# TPS53319_1_2V_Buck_Converter.net
KiCad netlist of a schematic drawn in Altium Designer
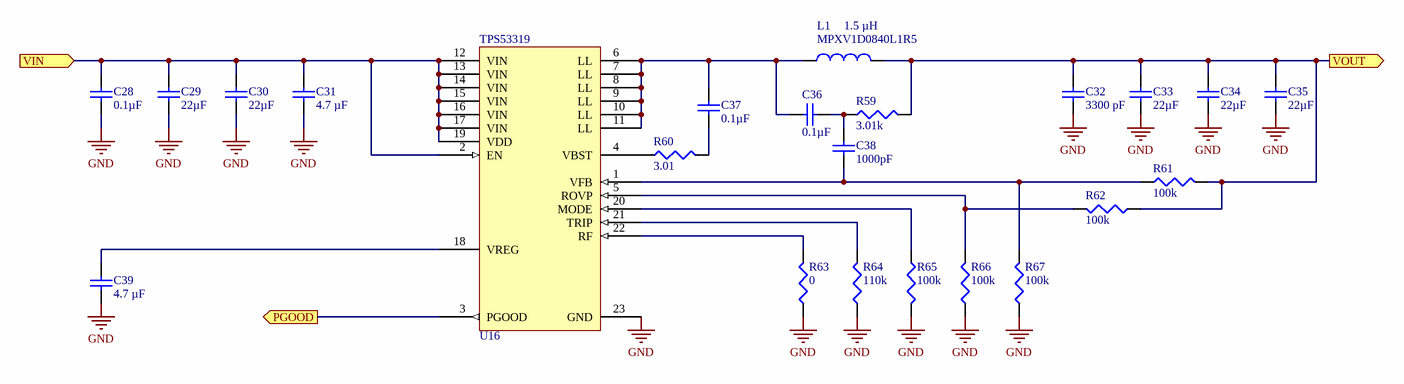
[diagram p0: TPS53319 1.2V Buck Converter.SchDoc]

(export (version "E")
  (design (tool "Eeschema 10.0.6"))
  (components
    (comp (ref "C28")
      (value "0.1µF")
      (footprint "TY-TWK107")
      (description "CAP CER 0.1UF 25V X7R 0306")
      (fields
        (field (name "PART NUMBER") "PC-TY-00817")
        (field (name "MANUFACTURER PART NUMBER") "TWK107B7104MVHT")
        (field (name "PUBLISHER") "AlbertaSat")
      )
      (libsource (lib "Database") (part "Cap"))
    )
    (comp (ref "C29")
      (value "22µF")
      (footprint "TDK-C3225")
      (description "CAP CER 22UF 25V X7R 1210")
      (fields
        (field (name "PART NUMBER") "PC-TDK-02965")
        (field (name "MANUFACTURER PART NUMBER") "C3225X7R1E226M250AB")
        (field (name "PUBLISHER") "AlbertaSat")
      )
      (libsource (lib "Database") (part "Cap"))
    )
    (comp (ref "C30")
      (value "22µF")
      (footprint "TDK-C3225")
      (description "CAP CER 22UF 25V X7R 1210")
      (fields
        (field (name "PART NUMBER") "PC-TDK-02965")
        (field (name "MANUFACTURER PART NUMBER") "C3225X7R1E226M250AB")
        (field (name "PUBLISHER") "AlbertaSat")
      )
      (libsource (lib "Database") (part "Cap"))
    )
    (comp (ref "C31")
      (value "4.7 µF")
      (footprint "MUR-GRM188")
      (description "CAP CER 4.7UF 16V X7R 0603")
      (fields
        (field (name "PART NUMBER") "10165")
        (field (name "MANUFACTURER PART NUMBER") "GRM188Z71C475KE21D")
        (field (name "PUBLISHER") "Altium Limited")
      )
      (libsource (lib "Database") (part "Cap"))
    )
    (comp (ref "C32")
      (value "3300 pF")
      (footprint "KEM-0402BB")
      (description "CAP CER 3300PF 50V X7R 0402")
      (fields
        (field (name "PART NUMBER") "PC-KEM-03166")
        (field (name "MANUFACTURER PART NUMBER") "C0402C332K5RAC7867")
        (field (name "PUBLISHER") "AlbertaSat")
      )
      (libsource (lib "Database") (part "Cap"))
    )
    (comp (ref "C33")
      (value "22µF")
      (footprint "TDK-C3225")
      (description "CAP CER 22UF 25V X7R 1210")
      (fields
        (field (name "PART NUMBER") "PC-TDK-02965")
        (field (name "MANUFACTURER PART NUMBER") "C3225X7R1E226M250AB")
        (field (name "PUBLISHER") "AlbertaSat")
      )
      (libsource (lib "Database") (part "Cap"))
    )
    (comp (ref "C34")
      (value "22µF")
      (footprint "TDK-C3225")
      (description "CAP CER 22UF 25V X7R 1210")
      (fields
        (field (name "PART NUMBER") "PC-TDK-02965")
        (field (name "MANUFACTURER PART NUMBER") "C3225X7R1E226M250AB")
        (field (name "PUBLISHER") "AlbertaSat")
      )
      (libsource (lib "Database") (part "Cap"))
    )
    (comp (ref "C35")
      (value "22µF")
      (footprint "TDK-C3225")
      (description "CAP CER 22UF 25V X7R 1210")
      (fields
        (field (name "PART NUMBER") "PC-TDK-02965")
        (field (name "MANUFACTURER PART NUMBER") "C3225X7R1E226M250AB")
        (field (name "PUBLISHER") "AlbertaSat")
      )
      (libsource (lib "Database") (part "Cap"))
    )
    (comp (ref "C36")
      (value "0.1µF")
      (footprint "TY-TWK107")
      (description "CAP CER 0.1UF 25V X7R 0306")
      (fields
        (field (name "PART NUMBER") "PC-TY-00817")
        (field (name "MANUFACTURER PART NUMBER") "TWK107B7104MVHT")
        (field (name "PUBLISHER") "AlbertaSat")
      )
      (libsource (lib "Database") (part "Cap"))
    )
    (comp (ref "C37")
      (value "0.1µF")
      (footprint "TY-TWK107")
      (description "CAP CER 0.1UF 25V X7R 0306")
      (fields
        (field (name "PART NUMBER") "PC-TY-00817")
        (field (name "MANUFACTURER PART NUMBER") "TWK107B7104MVHT")
        (field (name "PUBLISHER") "AlbertaSat")
      )
      (libsource (lib "Database") (part "Cap"))
    )
    (comp (ref "C38")
      (value "1000pF")
      (footprint "TDK-CGA2B")
      (description "CAP CER 1000PF 100V C0G 0402")
      (fields
        (field (name "PART NUMBER") "PC-TDK-01454")
        (field (name "MANUFACTURER PART NUMBER") "CGA2B1C0G2A102J050BC")
        (field (name "PUBLISHER") "AlbertaSat")
      )
      (libsource (lib "Database") (part "Cap"))
    )
    (comp (ref "C39")
      (value "4.7 µF")
      (footprint "MUR-GRM188")
      (description "CAP CER 4.7UF 16V X7R 0603")
      (fields
        (field (name "PART NUMBER") "10165")
        (field (name "MANUFACTURER PART NUMBER") "GRM188Z71C475KE21D")
        (field (name "PUBLISHER") "Altium Limited")
      )
      (libsource (lib "Database") (part "Cap"))
    )
    (comp (ref "L1")
      (value "1.5 µH")
      (footprint "KEM-MPXV1D0840")
      (description "FIXED IND 1.5UH 16.2A 6.8MOHM SM")
      (fields
        (field (name "PART NUMBER") "PL-KEM-03165")
        (field (name "MANUFACTURER PART NUMBER") "MPXV1D0840L1R5")
        (field (name "TOLERANCE") "±20%")
        (field (name "PUBLISHER") "AlbertaSat")
      )
      (libsource (lib "Database") (part "Inductor"))
    )
    (comp (ref "R59")
      (value "3.01k")
      (footprint "VSH-CRCW0201")
      (description "RES SMD 3.01K OHM 1% 1/20W 0201")
      (fields
        (field (name "PART NUMBER") "PR-VSH-00325")
        (field (name "MANUFACTURER PART NUMBER") "CRCW02013K01FKED")
        (field (name "PUBLISHER") "AlbertaSat")
      )
      (libsource (lib "Database") (part "Res3"))
    )
    (comp (ref "R60")
      (value "3.01")
      (footprint "VSH-CRCW0201")
      (description "CRCW0201 - 200/+400 3R01 1% ET7")
      (fields
        (field (name "PART NUMBER") "PR-VSH-00326")
        (field (name "MANUFACTURER PART NUMBER") "CRCW02013R01FXED")
        (field (name "PUBLISHER") "AlbertaSat")
      )
      (libsource (lib "Database") (part "Res3"))
    )
    (comp (ref "R61")
      (value "100k")
      (footprint "PANA-ERJ2R")
      (description "RES SMD 100K OHM 1% 1/10W 0402")
      (fields
        (field (name "PART NUMBER") "18739")
        (field (name "MANUFACTURER PART NUMBER") "ERJ-2RKF1003X")
        (field (name "PUBLISHER") "Altium Limited")
      )
      (libsource (lib "Database") (part "Res3"))
    )
    (comp (ref "R62")
      (value "100k")
      (footprint "PANA-ERJ2R")
      (description "RES SMD 100K OHM 1% 1/10W 0402")
      (fields
        (field (name "PART NUMBER") "18739")
        (field (name "MANUFACTURER PART NUMBER") "ERJ-2RKF1003X")
        (field (name "PUBLISHER") "Altium Limited")
      )
      (libsource (lib "Database") (part "Res3"))
    )
    (comp (ref "R63")
      (value "0")
      (footprint "PANA-ERJ2G")
      (description "RES SMD 0.0OHM JUMPER 1/10W 0402")
      (fields (field (name "PART NUMBER") "13127") (field (name "MANUFACTURER PART NUMBER") "ERJ-2GE0R00X"))
      (libsource (lib "Database") (part "Jumper3"))
    )
    (comp (ref "R64")
      (value "110k")
      (footprint "PANA-ERJ2R")
      (description "RES SMD 110K OHM 1% 1/10W 0402")
      (fields
        (field (name "PART NUMBER") "18785")
        (field (name "MANUFACTURER PART NUMBER") "ERJ-2RKF1103X")
        (field (name "PUBLISHER") "Altium Limited")
      )
      (libsource (lib "Database") (part "Res3"))
    )
    (comp (ref "R65")
      (value "100k")
      (footprint "PANA-ERJ2R")
      (description "RES SMD 100K OHM 1% 1/10W 0402")
      (fields
        (field (name "PART NUMBER") "18739")
        (field (name "MANUFACTURER PART NUMBER") "ERJ-2RKF1003X")
        (field (name "PUBLISHER") "Altium Limited")
      )
      (libsource (lib "Database") (part "Res3"))
    )
    (comp (ref "R66")
      (value "100k")
      (footprint "PANA-ERJ2R")
      (description "RES SMD 100K OHM 1% 1/10W 0402")
      (fields
        (field (name "PART NUMBER") "18739")
        (field (name "MANUFACTURER PART NUMBER") "ERJ-2RKF1003X")
        (field (name "PUBLISHER") "Altium Limited")
      )
      (libsource (lib "Database") (part "Res3"))
    )
    (comp (ref "R67")
      (value "100k")
      (footprint "PANA-ERJ2R")
      (description "RES SMD 100K OHM 1% 1/10W 0402")
      (fields
        (field (name "PART NUMBER") "18739")
        (field (name "MANUFACTURER PART NUMBER") "ERJ-2RKF1003X")
        (field (name "PUBLISHER") "Altium Limited")
      )
      (libsource (lib "Database") (part "Res3"))
    )
    (comp (ref "U16")
      (value "TPS53319")
      (footprint "TI-R-PSON-N22")
      (description "IC REG BUCK ADJUSTABLE 14A 22SON")
      (fields (field (name "PART NUMBER") "145") (field (name "MANUFACTURER PART NUMBER") "TPS53319DQPT"))
      (libsource (lib "Database") (part "TPS53319DQPT"))
    )
  )
  (nets
    (net (code "1") (name "/PGOOD") (class "Default")
      (node (ref "U16") (pin "3") (pinfunction "PGOOD_3") (pintype "output"))
    )
    (net (code "2") (name "/VIN") (class "Default")
      (node (ref "C28") (pin "2") (pinfunction "2_2") (pintype "passive"))
      (node (ref "C29") (pin "2") (pinfunction "2_2") (pintype "passive"))
      (node (ref "C30") (pin "2") (pinfunction "2_2") (pintype "passive"))
      (node (ref "C31") (pin "2") (pinfunction "2_2") (pintype "passive"))
      (node (ref "U16") (pin "12") (pinfunction "VIN_12") (pintype "power_in"))
      (node (ref "U16") (pin "13") (pinfunction "VIN_13") (pintype "power_in"))
      (node (ref "U16") (pin "14") (pinfunction "VIN_14") (pintype "power_in"))
      (node (ref "U16") (pin "15") (pinfunction "VIN_15") (pintype "power_in"))
      (node (ref "U16") (pin "16") (pinfunction "VIN_16") (pintype "power_in"))
      (node (ref "U16") (pin "17") (pinfunction "VIN_17") (pintype "power_in"))
      (node (ref "U16") (pin "19") (pinfunction "VDD_19") (pintype "power_in"))
      (node (ref "U16") (pin "2") (pinfunction "EN_2") (pintype "input"))
    )
    (net (code "3") (name "/VOUT") (class "Default")
      (node (ref "C32") (pin "2") (pinfunction "2_2") (pintype "passive"))
      (node (ref "C33") (pin "2") (pinfunction "2_2") (pintype "passive"))
      (node (ref "C34") (pin "2") (pinfunction "2_2") (pintype "passive"))
      (node (ref "C35") (pin "2") (pinfunction "2_2") (pintype "passive"))
      (node (ref "L1") (pin "2") (pinfunction "2_2") (pintype "passive"))
      (node (ref "R59") (pin "2") (pinfunction "2_2") (pintype "passive"))
      (node (ref "R61") (pin "2") (pinfunction "2_2") (pintype "passive"))
      (node (ref "R62") (pin "1") (pinfunction "1_1") (pintype "passive"))
    )
    (net (code "4") (name "GND") (class "Default")
      (node (ref "C28") (pin "1") (pinfunction "1_1") (pintype "passive"))
      (node (ref "C29") (pin "1") (pinfunction "1_1") (pintype "passive"))
      (node (ref "C30") (pin "1") (pinfunction "1_1") (pintype "passive"))
      (node (ref "C31") (pin "1") (pinfunction "1_1") (pintype "passive"))
      (node (ref "C32") (pin "1") (pinfunction "1_1") (pintype "passive"))
      (node (ref "C33") (pin "1") (pinfunction "1_1") (pintype "passive"))
      (node (ref "C34") (pin "1") (pinfunction "1_1") (pintype "passive"))
      (node (ref "C35") (pin "1") (pinfunction "1_1") (pintype "passive"))
      (node (ref "C39") (pin "1") (pinfunction "1_1") (pintype "passive"))
      (node (ref "R63") (pin "1") (pinfunction "1_1") (pintype "passive"))
      (node (ref "R64") (pin "1") (pinfunction "1_1") (pintype "passive"))
      (node (ref "R65") (pin "1") (pinfunction "1_1") (pintype "passive"))
      (node (ref "R66") (pin "1") (pinfunction "1_1") (pintype "passive"))
      (node (ref "R67") (pin "1") (pinfunction "1_1") (pintype "passive"))
      (node (ref "U16") (pin "23") (pinfunction "GND_23") (pintype "power_in"))
    )
    (net (code "5") (name "Net-(C36-Pad1)") (class "Default")
      (node (ref "C36") (pin "1") (pinfunction "1_1") (pintype "passive"))
      (node (ref "C38") (pin "1") (pinfunction "1_1") (pintype "passive"))
      (node (ref "R59") (pin "1") (pinfunction "1_1") (pintype "passive"))
    )
    (net (code "6") (name "Net-(C36-Pad2)") (class "Default")
      (node (ref "C36") (pin "2") (pinfunction "2_2") (pintype "passive"))
      (node (ref "C37") (pin "2") (pinfunction "2_2") (pintype "passive"))
      (node (ref "L1") (pin "1") (pinfunction "1_1") (pintype "passive"))
      (node (ref "U16") (pin "10") (pinfunction "LL_10") (pintype "power_in"))
      (node (ref "U16") (pin "11") (pinfunction "LL_11") (pintype "power_in"))
      (node (ref "U16") (pin "6") (pinfunction "LL_6") (pintype "power_in"))
      (node (ref "U16") (pin "7") (pinfunction "LL_7") (pintype "power_in"))
      (node (ref "U16") (pin "8") (pinfunction "LL_8") (pintype "power_in"))
      (node (ref "U16") (pin "9") (pinfunction "LL_9") (pintype "power_in"))
    )
    (net (code "7") (name "Net-(C37-Pad1)") (class "Default")
      (node (ref "C37") (pin "1") (pinfunction "1_1") (pintype "passive"))
      (node (ref "R60") (pin "2") (pinfunction "2_2") (pintype "passive"))
    )
    (net (code "8") (name "Net-(U16-MODE)") (class "Default")
      (node (ref "R65") (pin "2") (pinfunction "2_2") (pintype "passive"))
      (node (ref "U16") (pin "20") (pinfunction "MODE_20") (pintype "input"))
    )
    (net (code "9") (name "Net-(U16-RF)") (class "Default")
      (node (ref "R63") (pin "2") (pinfunction "2_2") (pintype "passive"))
      (node (ref "U16") (pin "22") (pinfunction "RF_22") (pintype "input"))
    )
    (net (code "10") (name "Net-(U16-ROVP)") (class "Default")
      (node (ref "R62") (pin "2") (pinfunction "2_2") (pintype "passive"))
      (node (ref "R66") (pin "2") (pinfunction "2_2") (pintype "passive"))
      (node (ref "U16") (pin "5") (pinfunction "ROVP_5") (pintype "input"))
    )
    (net (code "11") (name "Net-(U16-TRIP)") (class "Default")
      (node (ref "R64") (pin "2") (pinfunction "2_2") (pintype "passive"))
      (node (ref "U16") (pin "21") (pinfunction "TRIP_21") (pintype "input"))
    )
    (net (code "12") (name "Net-(U16-VBST)") (class "Default")
      (node (ref "R60") (pin "1") (pinfunction "1_1") (pintype "passive"))
      (node (ref "U16") (pin "4") (pinfunction "VBST_4") (pintype "power_in"))
    )
    (net (code "13") (name "Net-(U16-VFB)") (class "Default")
      (node (ref "C38") (pin "2") (pinfunction "2_2") (pintype "passive"))
      (node (ref "R61") (pin "1") (pinfunction "1_1") (pintype "passive"))
      (node (ref "R67") (pin "2") (pinfunction "2_2") (pintype "passive"))
      (node (ref "U16") (pin "1") (pinfunction "VFB_1") (pintype "input"))
    )
    (net (code "14") (name "Net-(U16-VREG)") (class "Default")
      (node (ref "C39") (pin "2") (pinfunction "2_2") (pintype "passive"))
      (node (ref "U16") (pin "18") (pinfunction "VREG_18") (pintype "passive"))
    )
  )
)
